# 2_classyTKL_MX_matrix.net
KiCad netlist of a schematic drawn in Altium Designer
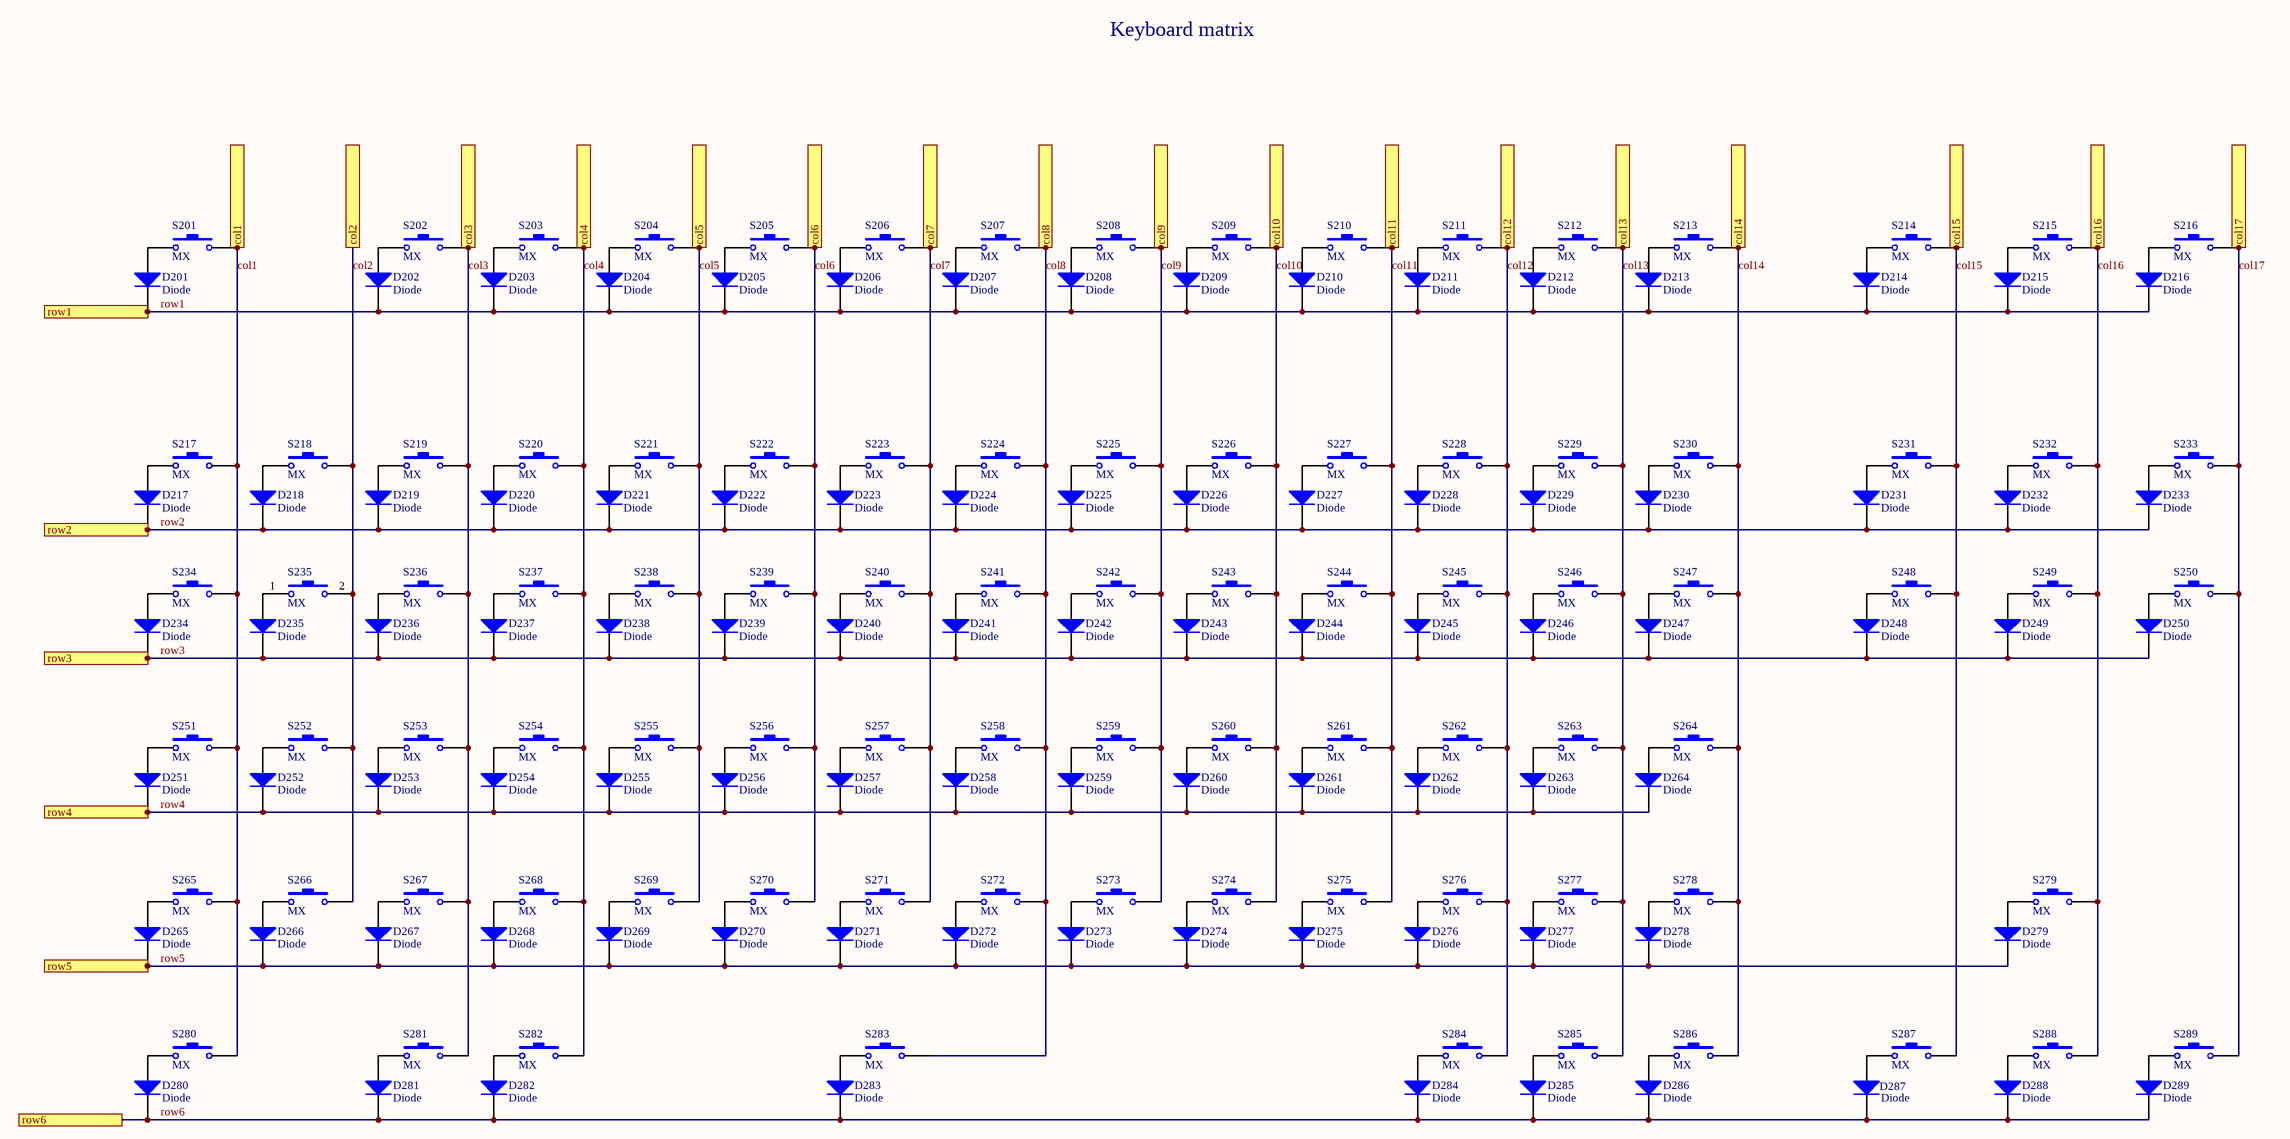
[diagram p0: 2_classyTKL_MX_matrix.SchDoc]

(export (version "E")
  (design (tool "Eeschema 10.0.6"))
  (components
    (comp (ref "D201")
      (value "Diode")
      (footprint "SOD-123")
      (description "Default Diode")
      (fields (field (name "LCSC PART #") "C81598") (field (name "MRF.PART") "1N4148W"))
      (libsource (lib "Miscellaneous Devices") (part "Diode"))
    )
    (comp (ref "D202")
      (value "Diode")
      (footprint "SOD-123")
      (description "Default Diode")
      (fields (field (name "LCSC PART #") "C81598") (field (name "MRF.PART") "1N4148W"))
      (libsource (lib "Miscellaneous Devices") (part "Diode"))
    )
    (comp (ref "D203")
      (value "Diode")
      (footprint "SOD-123")
      (description "Default Diode")
      (fields (field (name "LCSC PART #") "C81598") (field (name "MRF.PART") "1N4148W"))
      (libsource (lib "Miscellaneous Devices") (part "Diode"))
    )
    (comp (ref "D204")
      (value "Diode")
      (footprint "SOD-123")
      (description "Default Diode")
      (fields (field (name "LCSC PART #") "C81598") (field (name "MRF.PART") "1N4148W"))
      (libsource (lib "Miscellaneous Devices") (part "Diode"))
    )
    (comp (ref "D205")
      (value "Diode")
      (footprint "SOD-123")
      (description "Default Diode")
      (fields (field (name "LCSC PART #") "C81598") (field (name "MRF.PART") "1N4148W"))
      (libsource (lib "Miscellaneous Devices") (part "Diode"))
    )
    (comp (ref "D206")
      (value "Diode")
      (footprint "SOD-123")
      (description "Default Diode")
      (fields (field (name "LCSC PART #") "C81598") (field (name "MRF.PART") "1N4148W"))
      (libsource (lib "Miscellaneous Devices") (part "Diode"))
    )
    (comp (ref "D207")
      (value "Diode")
      (footprint "SOD-123")
      (description "Default Diode")
      (fields (field (name "LCSC PART #") "C81598") (field (name "MRF.PART") "1N4148W"))
      (libsource (lib "Miscellaneous Devices") (part "Diode"))
    )
    (comp (ref "D208")
      (value "Diode")
      (footprint "SOD-123")
      (description "Default Diode")
      (fields (field (name "LCSC PART #") "C81598") (field (name "MRF.PART") "1N4148W"))
      (libsource (lib "Miscellaneous Devices") (part "Diode"))
    )
    (comp (ref "D209")
      (value "Diode")
      (footprint "SOD-123")
      (description "Default Diode")
      (fields (field (name "LCSC PART #") "C81598") (field (name "MRF.PART") "1N4148W"))
      (libsource (lib "Miscellaneous Devices") (part "Diode"))
    )
    (comp (ref "D210")
      (value "Diode")
      (footprint "SOD-123")
      (description "Default Diode")
      (fields (field (name "LCSC PART #") "C81598") (field (name "MRF.PART") "1N4148W"))
      (libsource (lib "Miscellaneous Devices") (part "Diode"))
    )
    (comp (ref "D211")
      (value "Diode")
      (footprint "SOD-123")
      (description "Default Diode")
      (fields (field (name "LCSC PART #") "C81598") (field (name "MRF.PART") "1N4148W"))
      (libsource (lib "Miscellaneous Devices") (part "Diode"))
    )
    (comp (ref "D212")
      (value "Diode")
      (footprint "SOD-123")
      (description "Default Diode")
      (fields (field (name "LCSC PART #") "C81598") (field (name "MRF.PART") "1N4148W"))
      (libsource (lib "Miscellaneous Devices") (part "Diode"))
    )
    (comp (ref "D213")
      (value "Diode")
      (footprint "SOD-123")
      (description "Default Diode")
      (fields (field (name "LCSC PART #") "C81598") (field (name "MRF.PART") "1N4148W"))
      (libsource (lib "Miscellaneous Devices") (part "Diode"))
    )
    (comp (ref "D214")
      (value "Diode")
      (footprint "SOD-123")
      (description "Default Diode")
      (fields (field (name "LCSC PART #") "C81598") (field (name "MRF.PART") "1N4148W"))
      (libsource (lib "Miscellaneous Devices") (part "Diode"))
    )
    (comp (ref "D215")
      (value "Diode")
      (footprint "SOD-123")
      (description "Default Diode")
      (fields (field (name "LCSC PART #") "C81598") (field (name "MRF.PART") "1N4148W"))
      (libsource (lib "Miscellaneous Devices") (part "Diode"))
    )
    (comp (ref "D216")
      (value "Diode")
      (footprint "SOD-123")
      (description "Default Diode")
      (fields (field (name "LCSC PART #") "C81598") (field (name "MRF.PART") "1N4148W"))
      (libsource (lib "Miscellaneous Devices") (part "Diode"))
    )
    (comp (ref "D217")
      (value "Diode")
      (footprint "SOD-123")
      (description "Default Diode")
      (fields (field (name "LCSC PART #") "C81598") (field (name "MRF.PART") "1N4148W"))
      (libsource (lib "Miscellaneous Devices") (part "Diode"))
    )
    (comp (ref "D218")
      (value "Diode")
      (footprint "SOD-123")
      (description "Default Diode")
      (fields (field (name "LCSC PART #") "C81598") (field (name "MRF.PART") "1N4148W"))
      (libsource (lib "Miscellaneous Devices") (part "Diode"))
    )
    (comp (ref "D219")
      (value "Diode")
      (footprint "SOD-123")
      (description "Default Diode")
      (fields (field (name "LCSC PART #") "C81598") (field (name "MRF.PART") "1N4148W"))
      (libsource (lib "Miscellaneous Devices") (part "Diode"))
    )
    (comp (ref "D220")
      (value "Diode")
      (footprint "SOD-123")
      (description "Default Diode")
      (fields (field (name "LCSC PART #") "C81598") (field (name "MRF.PART") "1N4148W"))
      (libsource (lib "Miscellaneous Devices") (part "Diode"))
    )
    (comp (ref "D221")
      (value "Diode")
      (footprint "SOD-123")
      (description "Default Diode")
      (fields (field (name "LCSC PART #") "C81598") (field (name "MRF.PART") "1N4148W"))
      (libsource (lib "Miscellaneous Devices") (part "Diode"))
    )
    (comp (ref "D222")
      (value "Diode")
      (footprint "SOD-123")
      (description "Default Diode")
      (fields (field (name "LCSC PART #") "C81598") (field (name "MRF.PART") "1N4148W"))
      (libsource (lib "Miscellaneous Devices") (part "Diode"))
    )
    (comp (ref "D223")
      (value "Diode")
      (footprint "SOD-123")
      (description "Default Diode")
      (fields (field (name "LCSC PART #") "C81598") (field (name "MRF.PART") "1N4148W"))
      (libsource (lib "Miscellaneous Devices") (part "Diode"))
    )
    (comp (ref "D224")
      (value "Diode")
      (footprint "SOD-123")
      (description "Default Diode")
      (fields (field (name "LCSC PART #") "C81598") (field (name "MRF.PART") "1N4148W"))
      (libsource (lib "Miscellaneous Devices") (part "Diode"))
    )
    (comp (ref "D225")
      (value "Diode")
      (footprint "SOD-123")
      (description "Default Diode")
      (fields (field (name "LCSC PART #") "C81598") (field (name "MRF.PART") "1N4148W"))
      (libsource (lib "Miscellaneous Devices") (part "Diode"))
    )
    (comp (ref "D226")
      (value "Diode")
      (footprint "SOD-123")
      (description "Default Diode")
      (fields (field (name "LCSC PART #") "C81598") (field (name "MRF.PART") "1N4148W"))
      (libsource (lib "Miscellaneous Devices") (part "Diode"))
    )
    (comp (ref "D227")
      (value "Diode")
      (footprint "SOD-123")
      (description "Default Diode")
      (fields (field (name "LCSC PART #") "C81598") (field (name "MRF.PART") "1N4148W"))
      (libsource (lib "Miscellaneous Devices") (part "Diode"))
    )
    (comp (ref "D228")
      (value "Diode")
      (footprint "SOD-123")
      (description "Default Diode")
      (fields (field (name "LCSC PART #") "C81598") (field (name "MRF.PART") "1N4148W"))
      (libsource (lib "Miscellaneous Devices") (part "Diode"))
    )
    (comp (ref "D229")
      (value "Diode")
      (footprint "SOD-123")
      (description "Default Diode")
      (fields (field (name "LCSC PART #") "C81598") (field (name "MRF.PART") "1N4148W"))
      (libsource (lib "Miscellaneous Devices") (part "Diode"))
    )
    (comp (ref "D230")
      (value "Diode")
      (footprint "SOD-123")
      (description "Default Diode")
      (fields (field (name "LCSC PART #") "C81598") (field (name "MRF.PART") "1N4148W"))
      (libsource (lib "Miscellaneous Devices") (part "Diode"))
    )
    (comp (ref "D231")
      (value "Diode")
      (footprint "SOD-123")
      (description "Default Diode")
      (fields (field (name "LCSC PART #") "C81598") (field (name "MRF.PART") "1N4148W"))
      (libsource (lib "Miscellaneous Devices") (part "Diode"))
    )
    (comp (ref "D232")
      (value "Diode")
      (footprint "SOD-123")
      (description "Default Diode")
      (fields (field (name "LCSC PART #") "C81598") (field (name "MRF.PART") "1N4148W"))
      (libsource (lib "Miscellaneous Devices") (part "Diode"))
    )
    (comp (ref "D233")
      (value "Diode")
      (footprint "SOD-123")
      (description "Default Diode")
      (fields (field (name "LCSC PART #") "C81598") (field (name "MRF.PART") "1N4148W"))
      (libsource (lib "Miscellaneous Devices") (part "Diode"))
    )
    (comp (ref "D234")
      (value "Diode")
      (footprint "SOD-123")
      (description "Default Diode")
      (fields (field (name "LCSC PART #") "C81598") (field (name "MRF.PART") "1N4148W"))
      (libsource (lib "Miscellaneous Devices") (part "Diode"))
    )
    (comp (ref "D235")
      (value "Diode")
      (footprint "SOD-123")
      (description "Default Diode")
      (fields (field (name "LCSC PART #") "C81598") (field (name "MRF.PART") "1N4148W"))
      (libsource (lib "Miscellaneous Devices") (part "Diode"))
    )
    (comp (ref "D236")
      (value "Diode")
      (footprint "SOD-123")
      (description "Default Diode")
      (fields (field (name "LCSC PART #") "C81598") (field (name "MRF.PART") "1N4148W"))
      (libsource (lib "Miscellaneous Devices") (part "Diode"))
    )
    (comp (ref "D237")
      (value "Diode")
      (footprint "SOD-123")
      (description "Default Diode")
      (fields (field (name "LCSC PART #") "C81598") (field (name "MRF.PART") "1N4148W"))
      (libsource (lib "Miscellaneous Devices") (part "Diode"))
    )
    (comp (ref "D238")
      (value "Diode")
      (footprint "SOD-123")
      (description "Default Diode")
      (fields (field (name "LCSC PART #") "C81598") (field (name "MRF.PART") "1N4148W"))
      (libsource (lib "Miscellaneous Devices") (part "Diode"))
    )
    (comp (ref "D239")
      (value "Diode")
      (footprint "SOD-123")
      (description "Default Diode")
      (fields (field (name "LCSC PART #") "C81598") (field (name "MRF.PART") "1N4148W"))
      (libsource (lib "Miscellaneous Devices") (part "Diode"))
    )
    (comp (ref "D240")
      (value "Diode")
      (footprint "SOD-123")
      (description "Default Diode")
      (fields (field (name "LCSC PART #") "C81598") (field (name "MRF.PART") "1N4148W"))
      (libsource (lib "Miscellaneous Devices") (part "Diode"))
    )
    (comp (ref "D241")
      (value "Diode")
      (footprint "SOD-123")
      (description "Default Diode")
      (fields (field (name "LCSC PART #") "C81598") (field (name "MRF.PART") "1N4148W"))
      (libsource (lib "Miscellaneous Devices") (part "Diode"))
    )
    (comp (ref "D242")
      (value "Diode")
      (footprint "SOD-123")
      (description "Default Diode")
      (fields (field (name "LCSC PART #") "C81598") (field (name "MRF.PART") "1N4148W"))
      (libsource (lib "Miscellaneous Devices") (part "Diode"))
    )
    (comp (ref "D243")
      (value "Diode")
      (footprint "SOD-123")
      (description "Default Diode")
      (fields (field (name "LCSC PART #") "C81598") (field (name "MRF.PART") "1N4148W"))
      (libsource (lib "Miscellaneous Devices") (part "Diode"))
    )
    (comp (ref "D244")
      (value "Diode")
      (footprint "SOD-123")
      (description "Default Diode")
      (fields (field (name "LCSC PART #") "C81598") (field (name "MRF.PART") "1N4148W"))
      (libsource (lib "Miscellaneous Devices") (part "Diode"))
    )
    (comp (ref "D245")
      (value "Diode")
      (footprint "SOD-123")
      (description "Default Diode")
      (fields (field (name "LCSC PART #") "C81598") (field (name "MRF.PART") "1N4148W"))
      (libsource (lib "Miscellaneous Devices") (part "Diode"))
    )
    (comp (ref "D246")
      (value "Diode")
      (footprint "SOD-123")
      (description "Default Diode")
      (fields (field (name "LCSC PART #") "C81598") (field (name "MRF.PART") "1N4148W"))
      (libsource (lib "Miscellaneous Devices") (part "Diode"))
    )
    (comp (ref "D247")
      (value "Diode")
      (footprint "SOD-123")
      (description "Default Diode")
      (fields (field (name "LCSC PART #") "C81598") (field (name "MRF.PART") "1N4148W"))
      (libsource (lib "Miscellaneous Devices") (part "Diode"))
    )
    (comp (ref "D248")
      (value "Diode")
      (footprint "SOD-123")
      (description "Default Diode")
      (fields (field (name "LCSC PART #") "C81598") (field (name "MRF.PART") "1N4148W"))
      (libsource (lib "Miscellaneous Devices") (part "Diode"))
    )
    (comp (ref "D249")
      (value "Diode")
      (footprint "SOD-123")
      (description "Default Diode")
      (fields (field (name "LCSC PART #") "C81598") (field (name "MRF.PART") "1N4148W"))
      (libsource (lib "Miscellaneous Devices") (part "Diode"))
    )
    (comp (ref "D250")
      (value "Diode")
      (footprint "SOD-123")
      (description "Default Diode")
      (fields (field (name "LCSC PART #") "C81598") (field (name "MRF.PART") "1N4148W"))
      (libsource (lib "Miscellaneous Devices") (part "Diode"))
    )
    (comp (ref "D251")
      (value "Diode")
      (footprint "SOD-123")
      (description "Default Diode")
      (fields (field (name "LCSC PART #") "C81598") (field (name "MRF.PART") "1N4148W"))
      (libsource (lib "Miscellaneous Devices") (part "Diode"))
    )
    (comp (ref "D252")
      (value "Diode")
      (footprint "SOD-123")
      (description "Default Diode")
      (fields (field (name "LCSC PART #") "C81598") (field (name "MRF.PART") "1N4148W"))
      (libsource (lib "Miscellaneous Devices") (part "Diode"))
    )
    (comp (ref "D253")
      (value "Diode")
      (footprint "SOD-123")
      (description "Default Diode")
      (fields (field (name "LCSC PART #") "C81598") (field (name "MRF.PART") "1N4148W"))
      (libsource (lib "Miscellaneous Devices") (part "Diode"))
    )
    (comp (ref "D254")
      (value "Diode")
      (footprint "SOD-123")
      (description "Default Diode")
      (fields (field (name "LCSC PART #") "C81598") (field (name "MRF.PART") "1N4148W"))
      (libsource (lib "Miscellaneous Devices") (part "Diode"))
    )
    (comp (ref "D255")
      (value "Diode")
      (footprint "SOD-123")
      (description "Default Diode")
      (fields (field (name "LCSC PART #") "C81598") (field (name "MRF.PART") "1N4148W"))
      (libsource (lib "Miscellaneous Devices") (part "Diode"))
    )
    (comp (ref "D256")
      (value "Diode")
      (footprint "SOD-123")
      (description "Default Diode")
      (fields (field (name "LCSC PART #") "C81598") (field (name "MRF.PART") "1N4148W"))
      (libsource (lib "Miscellaneous Devices") (part "Diode"))
    )
    (comp (ref "D257")
      (value "Diode")
      (footprint "SOD-123")
      (description "Default Diode")
      (fields (field (name "LCSC PART #") "C81598") (field (name "MRF.PART") "1N4148W"))
      (libsource (lib "Miscellaneous Devices") (part "Diode"))
    )
    (comp (ref "D258")
      (value "Diode")
      (footprint "SOD-123")
      (description "Default Diode")
      (fields (field (name "LCSC PART #") "C81598") (field (name "MRF.PART") "1N4148W"))
      (libsource (lib "Miscellaneous Devices") (part "Diode"))
    )
    (comp (ref "D259")
      (value "Diode")
      (footprint "SOD-123")
      (description "Default Diode")
      (fields (field (name "LCSC PART #") "C81598") (field (name "MRF.PART") "1N4148W"))
      (libsource (lib "Miscellaneous Devices") (part "Diode"))
    )
    (comp (ref "D260")
      (value "Diode")
      (footprint "SOD-123")
      (description "Default Diode")
      (fields (field (name "LCSC PART #") "C81598") (field (name "MRF.PART") "1N4148W"))
      (libsource (lib "Miscellaneous Devices") (part "Diode"))
    )
    (comp (ref "D261")
      (value "Diode")
      (footprint "SOD-123")
      (description "Default Diode")
      (fields (field (name "LCSC PART #") "C81598") (field (name "MRF.PART") "1N4148W"))
      (libsource (lib "Miscellaneous Devices") (part "Diode"))
    )
    (comp (ref "D262")
      (value "Diode")
      (footprint "SOD-123")
      (description "Default Diode")
      (fields (field (name "LCSC PART #") "C81598") (field (name "MRF.PART") "1N4148W"))
      (libsource (lib "Miscellaneous Devices") (part "Diode"))
    )
    (comp (ref "D263")
      (value "Diode")
      (footprint "SOD-123")
      (description "Default Diode")
      (fields (field (name "LCSC PART #") "C81598") (field (name "MRF.PART") "1N4148W"))
      (libsource (lib "Miscellaneous Devices") (part "Diode"))
    )
    (comp (ref "D264")
      (value "Diode")
      (footprint "SOD-123")
      (description "Default Diode")
      (fields (field (name "LCSC PART #") "C81598") (field (name "MRF.PART") "1N4148W"))
      (libsource (lib "Miscellaneous Devices") (part "Diode"))
    )
    (comp (ref "D265")
      (value "Diode")
      (footprint "SOD-123")
      (description "Default Diode")
      (fields (field (name "LCSC PART #") "C81598") (field (name "MRF.PART") "1N4148W"))
      (libsource (lib "Miscellaneous Devices") (part "Diode"))
    )
    (comp (ref "D266")
      (value "Diode")
      (footprint "SOD-123")
      (description "Default Diode")
      (fields (field (name "LCSC PART #") "C81598") (field (name "MRF.PART") "1N4148W"))
      (libsource (lib "Miscellaneous Devices") (part "Diode"))
    )
    (comp (ref "D267")
      (value "Diode")
      (footprint "SOD-123")
      (description "Default Diode")
      (fields (field (name "LCSC PART #") "C81598") (field (name "MRF.PART") "1N4148W"))
      (libsource (lib "Miscellaneous Devices") (part "Diode"))
    )
    (comp (ref "D268")
      (value "Diode")
      (footprint "SOD-123")
      (description "Default Diode")
      (fields (field (name "LCSC PART #") "C81598") (field (name "MRF.PART") "1N4148W"))
      (libsource (lib "Miscellaneous Devices") (part "Diode"))
    )
    (comp (ref "D269")
      (value "Diode")
      (footprint "SOD-123")
      (description "Default Diode")
      (fields (field (name "LCSC PART #") "C81598") (field (name "MRF.PART") "1N4148W"))
      (libsource (lib "Miscellaneous Devices") (part "Diode"))
    )
    (comp (ref "D270")
      (value "Diode")
      (footprint "SOD-123")
      (description "Default Diode")
      (fields (field (name "LCSC PART #") "C81598") (field (name "MRF.PART") "1N4148W"))
      (libsource (lib "Miscellaneous Devices") (part "Diode"))
    )
    (comp (ref "D271")
      (value "Diode")
      (footprint "SOD-123")
      (description "Default Diode")
      (fields (field (name "LCSC PART #") "C81598") (field (name "MRF.PART") "1N4148W"))
      (libsource (lib "Miscellaneous Devices") (part "Diode"))
    )
    (comp (ref "D272")
      (value "Diode")
      (footprint "SOD-123")
      (description "Default Diode")
      (fields (field (name "LCSC PART #") "C81598") (field (name "MRF.PART") "1N4148W"))
      (libsource (lib "Miscellaneous Devices") (part "Diode"))
    )
    (comp (ref "D273")
      (value "Diode")
      (footprint "SOD-123")
      (description "Default Diode")
      (fields (field (name "LCSC PART #") "C81598") (field (name "MRF.PART") "1N4148W"))
      (libsource (lib "Miscellaneous Devices") (part "Diode"))
    )
    (comp (ref "D274")
      (value "Diode")
      (footprint "SOD-123")
      (description "Default Diode")
      (fields (field (name "LCSC PART #") "C81598") (field (name "MRF.PART") "1N4148W"))
      (libsource (lib "Miscellaneous Devices") (part "Diode"))
    )
    (comp (ref "D275")
      (value "Diode")
      (footprint "SOD-123")
      (description "Default Diode")
      (fields (field (name "LCSC PART #") "C81598") (field (name "MRF.PART") "1N4148W"))
      (libsource (lib "Miscellaneous Devices") (part "Diode"))
    )
    (comp (ref "D276")
      (value "Diode")
      (footprint "SOD-123")
      (description "Default Diode")
      (fields (field (name "LCSC PART #") "C81598") (field (name "MRF.PART") "1N4148W"))
      (libsource (lib "Miscellaneous Devices") (part "Diode"))
    )
    (comp (ref "D277")
      (value "Diode")
      (footprint "SOD-123")
      (description "Default Diode")
      (fields (field (name "LCSC PART #") "C81598") (field (name "MRF.PART") "1N4148W"))
      (libsource (lib "Miscellaneous Devices") (part "Diode"))
    )
    (comp (ref "D278")
      (value "Diode")
      (footprint "SOD-123")
      (description "Default Diode")
      (fields (field (name "LCSC PART #") "C81598") (field (name "MRF.PART") "1N4148W"))
      (libsource (lib "Miscellaneous Devices") (part "Diode"))
    )
    (comp (ref "D279")
      (value "Diode")
      (footprint "SOD-123")
      (description "Default Diode")
      (fields (field (name "LCSC PART #") "C81598") (field (name "MRF.PART") "1N4148W"))
      (libsource (lib "Miscellaneous Devices") (part "Diode"))
    )
    (comp (ref "D280")
      (value "Diode")
      (footprint "SOD-123")
      (description "Default Diode")
      (fields (field (name "LCSC PART #") "C81598") (field (name "MRF.PART") "1N4148W"))
      (libsource (lib "Miscellaneous Devices") (part "Diode"))
    )
    (comp (ref "D281")
      (value "Diode")
      (footprint "SOD-123")
      (description "Default Diode")
      (fields (field (name "LCSC PART #") "C81598") (field (name "MRF.PART") "1N4148W"))
      (libsource (lib "Miscellaneous Devices") (part "Diode"))
    )
    (comp (ref "D282")
      (value "Diode")
      (footprint "SOD-123")
      (description "Default Diode")
      (fields (field (name "LCSC PART #") "C81598") (field (name "MRF.PART") "1N4148W"))
      (libsource (lib "Miscellaneous Devices") (part "Diode"))
    )
    (comp (ref "D283")
      (value "Diode")
      (footprint "SOD-123")
      (description "Default Diode")
      (fields (field (name "LCSC PART #") "C81598") (field (name "MRF.PART") "1N4148W"))
      (libsource (lib "Miscellaneous Devices") (part "Diode"))
    )
    (comp (ref "D284")
      (value "Diode")
      (footprint "SOD-123")
      (description "Default Diode")
      (fields (field (name "LCSC PART #") "C81598") (field (name "MRF.PART") "1N4148W"))
      (libsource (lib "Miscellaneous Devices") (part "Diode"))
    )
    (comp (ref "D285")
      (value "Diode")
      (footprint "SOD-123")
      (description "Default Diode")
      (fields (field (name "LCSC PART #") "C81598") (field (name "MRF.PART") "1N4148W"))
      (libsource (lib "Miscellaneous Devices") (part "Diode"))
    )
    (comp (ref "D286")
      (value "Diode")
      (footprint "SOD-123")
      (description "Default Diode")
      (fields (field (name "LCSC PART #") "C81598") (field (name "MRF.PART") "1N4148W"))
      (libsource (lib "Miscellaneous Devices") (part "Diode"))
    )
    (comp (ref "D287")
      (value "Diode")
      (footprint "SOD-123")
      (description "Default Diode")
      (fields (field (name "LCSC PART #") "C81598") (field (name "MRF.PART") "1N4148W"))
      (libsource (lib "Miscellaneous Devices") (part "Diode"))
    )
    (comp (ref "D288")
      (value "Diode")
      (footprint "SOD-123")
      (description "Default Diode")
      (fields (field (name "LCSC PART #") "C81598") (field (name "MRF.PART") "1N4148W"))
      (libsource (lib "Miscellaneous Devices") (part "Diode"))
    )
    (comp (ref "D289")
      (value "Diode")
      (footprint "SOD-123")
      (description "Default Diode")
      (fields (field (name "LCSC PART #") "C81598") (field (name "MRF.PART") "1N4148W"))
      (libsource (lib "Miscellaneous Devices") (part "Diode"))
    )
    (comp (ref "S201")
      (value "MX")
      (footprint "MX-switch - switched pol")
      (description "Switch")
      (libsource (lib "Miscellaneous Devices") (part "SW-PB"))
    )
    (comp (ref "S202")
      (value "MX")
      (footprint "MX-switch")
      (description "Switch")
      (libsource (lib "Miscellaneous Devices") (part "SW-PB"))
    )
    (comp (ref "S203")
      (value "MX")
      (footprint "MX-switch")
      (description "Switch")
      (libsource (lib "Miscellaneous Devices") (part "SW-PB"))
    )
    (comp (ref "S204")
      (value "MX")
      (footprint "MX-switch")
      (description "Switch")
      (libsource (lib "Miscellaneous Devices") (part "SW-PB"))
    )
    (comp (ref "S205")
      (value "MX")
      (footprint "MX-switch - switched pol")
      (description "Switch")
      (libsource (lib "Miscellaneous Devices") (part "SW-PB"))
    )
    (comp (ref "S206")
      (value "MX")
      (footprint "MX-switch")
      (description "Switch")
      (libsource (lib "Miscellaneous Devices") (part "SW-PB"))
    )
    (comp (ref "S207")
      (value "MX")
      (footprint "MX-switch")
      (description "Switch")
      (libsource (lib "Miscellaneous Devices") (part "SW-PB"))
    )
    (comp (ref "S208")
      (value "MX")
      (footprint "MX-switch")
      (description "Switch")
      (libsource (lib "Miscellaneous Devices") (part "SW-PB"))
    )
    (comp (ref "S209")
      (value "MX")
      (footprint "MX-switch")
      (description "Switch")
      (libsource (lib "Miscellaneous Devices") (part "SW-PB"))
    )
    (comp (ref "S210")
      (value "MX")
      (footprint "MX-switch")
      (description "Switch")
      (libsource (lib "Miscellaneous Devices") (part "SW-PB"))
    )
    (comp (ref "S211")
      (value "MX")
      (footprint "MX-switch")
      (description "Switch")
      (libsource (lib "Miscellaneous Devices") (part "SW-PB"))
    )
    (comp (ref "S212")
      (value "MX")
      (footprint "MX-switch")
      (description "Switch")
      (libsource (lib "Miscellaneous Devices") (part "SW-PB"))
    )
    (comp (ref "S213")
      (value "MX")
      (footprint "MX-switch")
      (description "Switch")
      (libsource (lib "Miscellaneous Devices") (part "SW-PB"))
    )
    (comp (ref "S214")
      (value "MX")
      (footprint "MX-switch")
      (description "Switch")
      (libsource (lib "Miscellaneous Devices") (part "SW-PB"))
    )
    (comp (ref "S215")
      (value "MX")
      (footprint "MX-switch")
      (description "Switch")
      (libsource (lib "Miscellaneous Devices") (part "SW-PB"))
    )
    (comp (ref "S216")
      (value "MX")
      (footprint "MX-switch")
      (description "Switch")
      (libsource (lib "Miscellaneous Devices") (part "SW-PB"))
    )
    (comp (ref "S217")
      (value "MX")
      (footprint "MX-switch - switched pol")
      (description "Switch")
      (libsource (lib "Miscellaneous Devices") (part "SW-PB"))
    )
    (comp (ref "S218")
      (value "MX")
      (footprint "MX-switch - switched pol")
      (description "Switch")
      (libsource (lib "Miscellaneous Devices") (part "SW-PB"))
    )
    (comp (ref "S219")
      (value "MX")
      (footprint "MX-switch - switched pol")
      (description "Switch")
      (libsource (lib "Miscellaneous Devices") (part "SW-PB"))
    )
    (comp (ref "S220")
      (value "MX")
      (footprint "MX-switch - switched pol")
      (description "Switch")
      (libsource (lib "Miscellaneous Devices") (part "SW-PB"))
    )
    (comp (ref "S221")
      (value "MX")
      (footprint "MX-switch - switched pol")
      (description "Switch")
      (libsource (lib "Miscellaneous Devices") (part "SW-PB"))
    )
    (comp (ref "S222")
      (value "MX")
      (footprint "MX-switch - switched pol")
      (description "Switch")
      (libsource (lib "Miscellaneous Devices") (part "SW-PB"))
    )
    (comp (ref "S223")
      (value "MX")
      (footprint "MX-switch - switched pol")
      (description "Switch")
      (libsource (lib "Miscellaneous Devices") (part "SW-PB"))
    )
    (comp (ref "S224")
      (value "MX")
      (footprint "MX-switch - switched pol")
      (description "Switch")
      (libsource (lib "Miscellaneous Devices") (part "SW-PB"))
    )
    (comp (ref "S225")
      (value "MX")
      (footprint "MX-switch - switched pol")
      (description "Switch")
      (libsource (lib "Miscellaneous Devices") (part "SW-PB"))
    )
    (comp (ref "S226")
      (value "MX")
      (footprint "MX-switch - switched pol")
      (description "Switch")
      (libsource (lib "Miscellaneous Devices") (part "SW-PB"))
    )
    (comp (ref "S227")
      (value "MX")
      (footprint "MX-switch - switched pol")
      (description "Switch")
      (libsource (lib "Miscellaneous Devices") (part "SW-PB"))
    )
    (comp (ref "S228")
      (value "MX")
      (footprint "MX-switch - switched pol")
      (description "Switch")
      (libsource (lib "Miscellaneous Devices") (part "SW-PB"))
    )
    (comp (ref "S229")
      (value "MX")
      (footprint "MX-switch - switched pol")
      (description "Switch")
      (libsource (lib "Miscellaneous Devices") (part "SW-PB"))
    )
    (comp (ref "S230")
      (value "MX")
      (footprint "MX-switch")
      (description "Switch")
      (libsource (lib "Miscellaneous Devices") (part "SW-PB"))
    )
    (comp (ref "S231")
      (value "MX")
      (footprint "MX-switch")
      (description "Switch")
      (libsource (lib "Miscellaneous Devices") (part "SW-PB"))
    )
    (comp (ref "S232")
      (value "MX")
      (footprint "MX-switch")
      (description "Switch")
      (libsource (lib "Miscellaneous Devices") (part "SW-PB"))
    )
    (comp (ref "S233")
      (value "MX")
      (footprint "MX-switch")
      (description "Switch")
      (libsource (lib "Miscellaneous Devices") (part "SW-PB"))
    )
    (comp (ref "S234")
      (value "MX")
      (footprint "MX-switch - 1.5U - switched pol")
      (description "TAB")
      (libsource (lib "Miscellaneous Devices") (part "SW-PB"))
    )
    (comp (ref "S235")
      (value "MX")
      (footprint "MX-switch - switched pol")
      (description "Switch")
      (libsource (lib "") (part "SW-PB_1"))
    )
    (comp (ref "S236")
      (value "MX")
      (footprint "MX-switch - switched pol")
      (description "Switch")
      (libsource (lib "Miscellaneous Devices") (part "SW-PB"))
    )
    (comp (ref "S237")
      (value "MX")
      (footprint "MX-switch - switched pol")
      (description "Switch")
      (libsource (lib "Miscellaneous Devices") (part "SW-PB"))
    )
    (comp (ref "S238")
      (value "MX")
      (footprint "MX-switch - switched pol")
      (description "Switch")
      (libsource (lib "Miscellaneous Devices") (part "SW-PB"))
    )
    (comp (ref "S239")
      (value "MX")
      (footprint "MX-switch - switched pol")
      (description "Switch")
      (libsource (lib "Miscellaneous Devices") (part "SW-PB"))
    )
    (comp (ref "S240")
      (value "MX")
      (footprint "MX-switch - switched pol")
      (description "Switch")
      (libsource (lib "Miscellaneous Devices") (part "SW-PB"))
    )
    (comp (ref "S241")
      (value "MX")
      (footprint "MX-switch - switched pol")
      (description "Switch")
      (libsource (lib "Miscellaneous Devices") (part "SW-PB"))
    )
    (comp (ref "S242")
      (value "MX")
      (footprint "MX-switch - switched pol")
      (description "Switch")
      (libsource (lib "Miscellaneous Devices") (part "SW-PB"))
    )
    (comp (ref "S243")
      (value "MX")
      (footprint "MX-switch - switched pol")
      (description "Switch")
      (libsource (lib "Miscellaneous Devices") (part "SW-PB"))
    )
    (comp (ref "S244")
      (value "MX")
      (footprint "MX-switch - switched pol")
      (description "Switch")
      (libsource (lib "Miscellaneous Devices") (part "SW-PB"))
    )
    (comp (ref "S245")
      (value "MX")
      (footprint "MX-switch - switched pol")
      (description "Switch")
      (libsource (lib "Miscellaneous Devices") (part "SW-PB"))
    )
    (comp (ref "S246")
      (value "MX")
      (footprint "MX-switch - switched pol")
      (description "Switch")
      (libsource (lib "Miscellaneous Devices") (part "SW-PB"))
    )
    (comp (ref "S247")
      (value "MX")
      (footprint "MX-switch - PIPE_ISO_ENTER")
      (description "Switch")
      (libsource (lib "Miscellaneous Devices") (part "SW-PB"))
    )
    (comp (ref "S248")
      (value "MX")
      (footprint "MX-switch")
      (description "Switch")
      (libsource (lib "Miscellaneous Devices") (part "SW-PB"))
    )
    (comp (ref "S249")
      (value "MX")
      (footprint "MX-switch")
      (description "Switch")
      (libsource (lib "Miscellaneous Devices") (part "SW-PB"))
    )
    (comp (ref "S250")
      (value "MX")
      (footprint "MX-switch")
      (description "Switch")
      (libsource (lib "Miscellaneous Devices") (part "SW-PB"))
    )
    (comp (ref "S251")
      (value "MX")
      (footprint "MX-switch - CAPS")
      (description "Switch")
      (libsource (lib "Miscellaneous Devices") (part "SW-PB"))
    )
    (comp (ref "S252")
      (value "MX")
      (footprint "MX-switch - switched pol")
      (description "Switch")
      (libsource (lib "Miscellaneous Devices") (part "SW-PB"))
    )
    (comp (ref "S253")
      (value "MX")
      (footprint "MX-switch - switched pol")
      (description "Switch")
      (libsource (lib "Miscellaneous Devices") (part "SW-PB"))
    )
    (comp (ref "S254")
      (value "MX")
      (footprint "MX-switch - switched pol")
      (description "Switch")
      (libsource (lib "Miscellaneous Devices") (part "SW-PB"))
    )
    (comp (ref "S255")
      (value "MX")
      (footprint "MX-switch - switched pol")
      (description "Switch")
      (libsource (lib "Miscellaneous Devices") (part "SW-PB"))
    )
    (comp (ref "S256")
      (value "MX")
      (footprint "MX-switch - switched pol")
      (description "Switch")
      (libsource (lib "Miscellaneous Devices") (part "SW-PB"))
    )
    (comp (ref "S257")
      (value "MX")
      (footprint "MX-switch - switched pol")
      (description "Switch")
      (libsource (lib "Miscellaneous Devices") (part "SW-PB"))
    )
    (comp (ref "S258")
      (value "MX")
      (footprint "MX-switch - switched pol")
      (description "Switch")
      (libsource (lib "Miscellaneous Devices") (part "SW-PB"))
    )
    (comp (ref "S259")
      (value "MX")
      (footprint "MX-switch - switched pol")
      (description "Switch")
      (libsource (lib "Miscellaneous Devices") (part "SW-PB"))
    )
    (comp (ref "S260")
      (value "MX")
      (footprint "MX-switch - switched pol")
      (description "Switch")
      (libsource (lib "Miscellaneous Devices") (part "SW-PB"))
    )
    (comp (ref "S261")
      (value "MX")
      (footprint "MX-switch - switched pol")
      (description "Switch")
      (libsource (lib "Miscellaneous Devices") (part "SW-PB"))
    )
    (comp (ref "S262")
      (value "MX")
      (footprint "MX-switch - switched pol")
      (description "Switch")
      (libsource (lib "Miscellaneous Devices") (part "SW-PB"))
    )
    (comp (ref "S263")
      (value "MX")
      (footprint "MX-switch - Enter_ANSI_ISO_KEY")
      (description "Switch")
      (libsource (lib "Miscellaneous Devices") (part "SW-PB"))
    )
    (comp (ref "S264")
      (value "MX")
      (footprint "MX-switch - backspace")
      (description "Switch")
      (libsource (lib "Miscellaneous Devices") (part "SW-PB"))
    )
    (comp (ref "S265")
      (value "MX")
      (footprint "MX-switch - Left shift")
      (description "Switch")
      (libsource (lib "Miscellaneous Devices") (part "SW-PB"))
    )
    (comp (ref "S266")
      (value "MX")
      (footprint "MX-switch - switched pol")
      (description "Switch")
      (libsource (lib "Miscellaneous Devices") (part "SW-PB"))
    )
    (comp (ref "S267")
      (value "MX")
      (footprint "MX-switch - switched pol")
      (description "Switch")
      (libsource (lib "Miscellaneous Devices") (part "SW-PB"))
    )
    (comp (ref "S268")
      (value "MX")
      (footprint "MX-switch - switched pol")
      (description "Switch")
      (libsource (lib "Miscellaneous Devices") (part "SW-PB"))
    )
    (comp (ref "S269")
      (value "MX")
      (footprint "MX-switch - switched pol")
      (description "Switch")
      (libsource (lib "Miscellaneous Devices") (part "SW-PB"))
    )
    (comp (ref "S270")
      (value "MX")
      (footprint "MX-switch - switched pol")
      (description "Switch")
      (libsource (lib "Miscellaneous Devices") (part "SW-PB"))
    )
    (comp (ref "S271")
      (value "MX")
      (footprint "MX-switch - switched pol")
      (description "Switch")
      (libsource (lib "Miscellaneous Devices") (part "SW-PB"))
    )
    (comp (ref "S272")
      (value "MX")
      (footprint "MX-switch - switched pol")
      (description "Switch")
      (libsource (lib "Miscellaneous Devices") (part "SW-PB"))
    )
    (comp (ref "S273")
      (value "MX")
      (footprint "MX-switch - switched pol")
      (description "Switch")
      (libsource (lib "Miscellaneous Devices") (part "SW-PB"))
    )
    (comp (ref "S274")
      (value "MX")
      (footprint "MX-switch - switched pol")
      (description "Switch")
      (libsource (lib "Miscellaneous Devices") (part "SW-PB"))
    )
    (comp (ref "S275")
      (value "MX")
      (footprint "MX-switch - switched pol")
      (description "Switch")
      (libsource (lib "Miscellaneous Devices") (part "SW-PB"))
    )
    (comp (ref "S276")
      (value "MX")
      (footprint "MX-switch - switched pol")
      (description "Switch")
      (libsource (lib "Miscellaneous Devices") (part "SW-PB"))
    )
    (comp (ref "S277")
      (value "MX")
      (footprint "MX-switch - right shift")
      (description "Switch")
      (libsource (lib "Miscellaneous Devices") (part "SW-PB"))
    )
    (comp (ref "S278")
      (value "MX")
      (footprint "MX-switch")
      (description "Switch")
      (libsource (lib "Miscellaneous Devices") (part "SW-PB"))
    )
    (comp (ref "S279")
      (value "MX")
      (footprint "MX-switch")
      (description "Switch")
      (libsource (lib "Miscellaneous Devices") (part "SW-PB"))
    )
    (comp (ref "S280")
      (value "MX")
      (footprint "MX-switch - 1.5U - switched pol")
      (description "Switch")
      (libsource (lib "Miscellaneous Devices") (part "SW-PB"))
    )
    (comp (ref "S281")
      (value "MX")
      (footprint "MX-switch")
      (description "Switch")
      (libsource (lib "Miscellaneous Devices") (part "SW-PB"))
    )
    (comp (ref "S282")
      (value "MX")
      (footprint "MX-switch - 1.5U")
      (description "Switch")
      (libsource (lib "Miscellaneous Devices") (part "SW-PB"))
    )
    (comp (ref "S283")
      (value "MX")
      (footprint "MX-switch - 7u space")
      (description "Switch")
      (libsource (lib "Miscellaneous Devices") (part "SW-PB"))
    )
    (comp (ref "S284")
      (value "MX")
      (footprint "MX-switch - 1.5U")
      (description "Switch")
      (libsource (lib "Miscellaneous Devices") (part "SW-PB"))
    )
    (comp (ref "S285")
      (value "MX")
      (footprint "MX-switch")
      (description "Switch")
      (libsource (lib "Miscellaneous Devices") (part "SW-PB"))
    )
    (comp (ref "S286")
      (value "MX")
      (footprint "MX-switch - 1.5U")
      (description "Switch")
      (libsource (lib "Miscellaneous Devices") (part "SW-PB"))
    )
    (comp (ref "S287")
      (value "MX")
      (footprint "MX-switch")
      (description "Switch")
      (libsource (lib "Miscellaneous Devices") (part "SW-PB"))
    )
    (comp (ref "S288")
      (value "MX")
      (footprint "MX-switch")
      (description "Switch")
      (libsource (lib "Miscellaneous Devices") (part "SW-PB"))
    )
    (comp (ref "S289")
      (value "MX")
      (footprint "MX-switch")
      (description "Switch")
      (libsource (lib "Miscellaneous Devices") (part "SW-PB"))
    )
  )
  (nets
    (net (code "1") (name "/col1") (class "Default")
      (node (ref "S201") (pin "2") (pinfunction "2_2") (pintype "passive"))
      (node (ref "S217") (pin "2") (pinfunction "2_2") (pintype "passive"))
      (node (ref "S234") (pin "2") (pinfunction "2_2") (pintype "passive"))
      (node (ref "S251") (pin "2") (pinfunction "2_2") (pintype "passive"))
      (node (ref "S265") (pin "2") (pinfunction "2_2") (pintype "passive"))
      (node (ref "S280") (pin "2") (pinfunction "2_2") (pintype "passive"))
    )
    (net (code "2") (name "/col2") (class "Default")
      (node (ref "S218") (pin "2") (pinfunction "2_2") (pintype "passive"))
      (node (ref "S235") (pin "2") (pinfunction "2_2") (pintype "passive"))
      (node (ref "S252") (pin "2") (pinfunction "2_2") (pintype "passive"))
      (node (ref "S266") (pin "2") (pinfunction "2_2") (pintype "passive"))
    )
    (net (code "3") (name "/col3") (class "Default")
      (node (ref "S202") (pin "2") (pinfunction "2_2") (pintype "passive"))
      (node (ref "S219") (pin "2") (pinfunction "2_2") (pintype "passive"))
      (node (ref "S236") (pin "2") (pinfunction "2_2") (pintype "passive"))
      (node (ref "S253") (pin "2") (pinfunction "2_2") (pintype "passive"))
      (node (ref "S267") (pin "2") (pinfunction "2_2") (pintype "passive"))
      (node (ref "S281") (pin "2") (pinfunction "2_2") (pintype "passive"))
    )
    (net (code "4") (name "/col4") (class "Default")
      (node (ref "S203") (pin "2") (pinfunction "2_2") (pintype "passive"))
      (node (ref "S220") (pin "2") (pinfunction "2_2") (pintype "passive"))
      (node (ref "S237") (pin "2") (pinfunction "2_2") (pintype "passive"))
      (node (ref "S254") (pin "2") (pinfunction "2_2") (pintype "passive"))
      (node (ref "S268") (pin "2") (pinfunction "2_2") (pintype "passive"))
      (node (ref "S282") (pin "2") (pinfunction "2_2") (pintype "passive"))
    )
    (net (code "5") (name "/col5") (class "Default")
      (node (ref "S204") (pin "2") (pinfunction "2_2") (pintype "passive"))
      (node (ref "S221") (pin "2") (pinfunction "2_2") (pintype "passive"))
      (node (ref "S238") (pin "2") (pinfunction "2_2") (pintype "passive"))
      (node (ref "S255") (pin "2") (pinfunction "2_2") (pintype "passive"))
      (node (ref "S269") (pin "2") (pinfunction "2_2") (pintype "passive"))
    )
    (net (code "6") (name "/col6") (class "Default")
      (node (ref "S205") (pin "2") (pinfunction "2_2") (pintype "passive"))
      (node (ref "S222") (pin "2") (pinfunction "2_2") (pintype "passive"))
      (node (ref "S239") (pin "2") (pinfunction "2_2") (pintype "passive"))
      (node (ref "S256") (pin "2") (pinfunction "2_2") (pintype "passive"))
      (node (ref "S270") (pin "2") (pinfunction "2_2") (pintype "passive"))
    )
    (net (code "7") (name "/col7") (class "Default")
      (node (ref "S206") (pin "2") (pinfunction "2_2") (pintype "passive"))
      (node (ref "S223") (pin "2") (pinfunction "2_2") (pintype "passive"))
      (node (ref "S240") (pin "2") (pinfunction "2_2") (pintype "passive"))
      (node (ref "S257") (pin "2") (pinfunction "2_2") (pintype "passive"))
      (node (ref "S271") (pin "2") (pinfunction "2_2") (pintype "passive"))
    )
    (net (code "8") (name "/col8") (class "Default")
      (node (ref "S207") (pin "2") (pinfunction "2_2") (pintype "passive"))
      (node (ref "S224") (pin "2") (pinfunction "2_2") (pintype "passive"))
      (node (ref "S241") (pin "2") (pinfunction "2_2") (pintype "passive"))
      (node (ref "S258") (pin "2") (pinfunction "2_2") (pintype "passive"))
      (node (ref "S272") (pin "2") (pinfunction "2_2") (pintype "passive"))
      (node (ref "S283") (pin "2") (pinfunction "2_2") (pintype "passive"))
    )
    (net (code "9") (name "/col9") (class "Default")
      (node (ref "S208") (pin "2") (pinfunction "2_2") (pintype "passive"))
      (node (ref "S225") (pin "2") (pinfunction "2_2") (pintype "passive"))
      (node (ref "S242") (pin "2") (pinfunction "2_2") (pintype "passive"))
      (node (ref "S259") (pin "2") (pinfunction "2_2") (pintype "passive"))
      (node (ref "S273") (pin "2") (pinfunction "2_2") (pintype "passive"))
    )
    (net (code "10") (name "/col10") (class "Default")
      (node (ref "S209") (pin "2") (pinfunction "2_2") (pintype "passive"))
      (node (ref "S226") (pin "2") (pinfunction "2_2") (pintype "passive"))
      (node (ref "S243") (pin "2") (pinfunction "2_2") (pintype "passive"))
      (node (ref "S260") (pin "2") (pinfunction "2_2") (pintype "passive"))
      (node (ref "S274") (pin "2") (pinfunction "2_2") (pintype "passive"))
    )
    (net (code "11") (name "/col11") (class "Default")
      (node (ref "S210") (pin "2") (pinfunction "2_2") (pintype "passive"))
      (node (ref "S227") (pin "2") (pinfunction "2_2") (pintype "passive"))
      (node (ref "S244") (pin "2") (pinfunction "2_2") (pintype "passive"))
      (node (ref "S261") (pin "2") (pinfunction "2_2") (pintype "passive"))
      (node (ref "S275") (pin "2") (pinfunction "2_2") (pintype "passive"))
    )
    (net (code "12") (name "/col12") (class "Default")
      (node (ref "S211") (pin "2") (pinfunction "2_2") (pintype "passive"))
      (node (ref "S228") (pin "2") (pinfunction "2_2") (pintype "passive"))
      (node (ref "S245") (pin "2") (pinfunction "2_2") (pintype "passive"))
      (node (ref "S262") (pin "2") (pinfunction "2_2") (pintype "passive"))
      (node (ref "S276") (pin "2") (pinfunction "2_2") (pintype "passive"))
      (node (ref "S284") (pin "2") (pinfunction "2_2") (pintype "passive"))
    )
    (net (code "13") (name "/col13") (class "Default")
      (node (ref "S212") (pin "2") (pinfunction "2_2") (pintype "passive"))
      (node (ref "S229") (pin "2") (pinfunction "2_2") (pintype "passive"))
      (node (ref "S246") (pin "2") (pinfunction "2_2") (pintype "passive"))
      (node (ref "S263") (pin "2") (pinfunction "2_2") (pintype "passive"))
      (node (ref "S277") (pin "2") (pinfunction "2_2") (pintype "passive"))
      (node (ref "S285") (pin "2") (pinfunction "2_2") (pintype "passive"))
    )
    (net (code "14") (name "/col14") (class "Default")
      (node (ref "S213") (pin "2") (pinfunction "2_2") (pintype "passive"))
      (node (ref "S230") (pin "2") (pinfunction "2_2") (pintype "passive"))
      (node (ref "S247") (pin "2") (pinfunction "2_2") (pintype "passive"))
      (node (ref "S264") (pin "2") (pinfunction "2_2") (pintype "passive"))
      (node (ref "S278") (pin "2") (pinfunction "2_2") (pintype "passive"))
      (node (ref "S286") (pin "2") (pinfunction "2_2") (pintype "passive"))
    )
    (net (code "15") (name "/col15") (class "Default")
      (node (ref "S214") (pin "2") (pinfunction "2_2") (pintype "passive"))
      (node (ref "S231") (pin "2") (pinfunction "2_2") (pintype "passive"))
      (node (ref "S248") (pin "2") (pinfunction "2_2") (pintype "passive"))
      (node (ref "S287") (pin "2") (pinfunction "2_2") (pintype "passive"))
    )
    (net (code "16") (name "/col16") (class "Default")
      (node (ref "S215") (pin "2") (pinfunction "2_2") (pintype "passive"))
      (node (ref "S232") (pin "2") (pinfunction "2_2") (pintype "passive"))
      (node (ref "S249") (pin "2") (pinfunction "2_2") (pintype "passive"))
      (node (ref "S279") (pin "2") (pinfunction "2_2") (pintype "passive"))
      (node (ref "S288") (pin "2") (pinfunction "2_2") (pintype "passive"))
    )
    (net (code "17") (name "/col17") (class "Default")
      (node (ref "S216") (pin "2") (pinfunction "2_2") (pintype "passive"))
      (node (ref "S233") (pin "2") (pinfunction "2_2") (pintype "passive"))
      (node (ref "S250") (pin "2") (pinfunction "2_2") (pintype "passive"))
      (node (ref "S289") (pin "2") (pinfunction "2_2") (pintype "passive"))
    )
    (net (code "18") (name "/row1") (class "Default")
      (node (ref "D201") (pin "2") (pinfunction "K_2") (pintype "passive"))
      (node (ref "D202") (pin "2") (pinfunction "K_2") (pintype "passive"))
      (node (ref "D203") (pin "2") (pinfunction "K_2") (pintype "passive"))
      (node (ref "D204") (pin "2") (pinfunction "K_2") (pintype "passive"))
      (node (ref "D205") (pin "2") (pinfunction "K_2") (pintype "passive"))
      (node (ref "D206") (pin "2") (pinfunction "K_2") (pintype "passive"))
      (node (ref "D207") (pin "2") (pinfunction "K_2") (pintype "passive"))
      (node (ref "D208") (pin "2") (pinfunction "K_2") (pintype "passive"))
      (node (ref "D209") (pin "2") (pinfunction "K_2") (pintype "passive"))
      (node (ref "D210") (pin "2") (pinfunction "K_2") (pintype "passive"))
      (node (ref "D211") (pin "2") (pinfunction "K_2") (pintype "passive"))
      (node (ref "D212") (pin "2") (pinfunction "K_2") (pintype "passive"))
      (node (ref "D213") (pin "2") (pinfunction "K_2") (pintype "passive"))
      (node (ref "D214") (pin "2") (pinfunction "K_2") (pintype "passive"))
      (node (ref "D215") (pin "2") (pinfunction "K_2") (pintype "passive"))
      (node (ref "D216") (pin "2") (pinfunction "K_2") (pintype "passive"))
    )
    (net (code "19") (name "/row2") (class "Default")
      (node (ref "D217") (pin "2") (pinfunction "K_2") (pintype "passive"))
      (node (ref "D218") (pin "2") (pinfunction "K_2") (pintype "passive"))
      (node (ref "D219") (pin "2") (pinfunction "K_2") (pintype "passive"))
      (node (ref "D220") (pin "2") (pinfunction "K_2") (pintype "passive"))
      (node (ref "D221") (pin "2") (pinfunction "K_2") (pintype "passive"))
      (node (ref "D222") (pin "2") (pinfunction "K_2") (pintype "passive"))
      (node (ref "D223") (pin "2") (pinfunction "K_2") (pintype "passive"))
      (node (ref "D224") (pin "2") (pinfunction "K_2") (pintype "passive"))
      (node (ref "D225") (pin "2") (pinfunction "K_2") (pintype "passive"))
      (node (ref "D226") (pin "2") (pinfunction "K_2") (pintype "passive"))
      (node (ref "D227") (pin "2") (pinfunction "K_2") (pintype "passive"))
      (node (ref "D228") (pin "2") (pinfunction "K_2") (pintype "passive"))
      (node (ref "D229") (pin "2") (pinfunction "K_2") (pintype "passive"))
      (node (ref "D230") (pin "2") (pinfunction "K_2") (pintype "passive"))
      (node (ref "D231") (pin "2") (pinfunction "K_2") (pintype "passive"))
      (node (ref "D232") (pin "2") (pinfunction "K_2") (pintype "passive"))
      (node (ref "D233") (pin "2") (pinfunction "K_2") (pintype "passive"))
    )
    (net (code "20") (name "/row3") (class "Default")
      (node (ref "D234") (pin "2") (pinfunction "K_2") (pintype "passive"))
      (node (ref "D235") (pin "2") (pinfunction "K_2") (pintype "passive"))
      (node (ref "D236") (pin "2") (pinfunction "K_2") (pintype "passive"))
      (node (ref "D237") (pin "2") (pinfunction "K_2") (pintype "passive"))
      (node (ref "D238") (pin "2") (pinfunction "K_2") (pintype "passive"))
      (node (ref "D239") (pin "2") (pinfunction "K_2") (pintype "passive"))
      (node (ref "D240") (pin "2") (pinfunction "K_2") (pintype "passive"))
      (node (ref "D241") (pin "2") (pinfunction "K_2") (pintype "passive"))
      (node (ref "D242") (pin "2") (pinfunction "K_2") (pintype "passive"))
      (node (ref "D243") (pin "2") (pinfunction "K_2") (pintype "passive"))
      (node (ref "D244") (pin "2") (pinfunction "K_2") (pintype "passive"))
      (node (ref "D245") (pin "2") (pinfunction "K_2") (pintype "passive"))
      (node (ref "D246") (pin "2") (pinfunction "K_2") (pintype "passive"))
      (node (ref "D247") (pin "2") (pinfunction "K_2") (pintype "passive"))
      (node (ref "D248") (pin "2") (pinfunction "K_2") (pintype "passive"))
      (node (ref "D249") (pin "2") (pinfunction "K_2") (pintype "passive"))
      (node (ref "D250") (pin "2") (pinfunction "K_2") (pintype "passive"))
    )
    (net (code "21") (name "/row4") (class "Default")
      (node (ref "D251") (pin "2") (pinfunction "K_2") (pintype "passive"))
      (node (ref "D252") (pin "2") (pinfunction "K_2") (pintype "passive"))
      (node (ref "D253") (pin "2") (pinfunction "K_2") (pintype "passive"))
      (node (ref "D254") (pin "2") (pinfunction "K_2") (pintype "passive"))
      (node (ref "D255") (pin "2") (pinfunction "K_2") (pintype "passive"))
      (node (ref "D256") (pin "2") (pinfunction "K_2") (pintype "passive"))
      (node (ref "D257") (pin "2") (pinfunction "K_2") (pintype "passive"))
      (node (ref "D258") (pin "2") (pinfunction "K_2") (pintype "passive"))
      (node (ref "D259") (pin "2") (pinfunction "K_2") (pintype "passive"))
      (node (ref "D260") (pin "2") (pinfunction "K_2") (pintype "passive"))
      (node (ref "D261") (pin "2") (pinfunction "K_2") (pintype "passive"))
      (node (ref "D262") (pin "2") (pinfunction "K_2") (pintype "passive"))
      (node (ref "D263") (pin "2") (pinfunction "K_2") (pintype "passive"))
      (node (ref "D264") (pin "2") (pinfunction "K_2") (pintype "passive"))
    )
    (net (code "22") (name "/row5") (class "Default")
      (node (ref "D265") (pin "2") (pinfunction "K_2") (pintype "passive"))
      (node (ref "D266") (pin "2") (pinfunction "K_2") (pintype "passive"))
      (node (ref "D267") (pin "2") (pinfunction "K_2") (pintype "passive"))
      (node (ref "D268") (pin "2") (pinfunction "K_2") (pintype "passive"))
      (node (ref "D269") (pin "2") (pinfunction "K_2") (pintype "passive"))
      (node (ref "D270") (pin "2") (pinfunction "K_2") (pintype "passive"))
      (node (ref "D271") (pin "2") (pinfunction "K_2") (pintype "passive"))
      (node (ref "D272") (pin "2") (pinfunction "K_2") (pintype "passive"))
      (node (ref "D273") (pin "2") (pinfunction "K_2") (pintype "passive"))
      (node (ref "D274") (pin "2") (pinfunction "K_2") (pintype "passive"))
      (node (ref "D275") (pin "2") (pinfunction "K_2") (pintype "passive"))
      (node (ref "D276") (pin "2") (pinfunction "K_2") (pintype "passive"))
      (node (ref "D277") (pin "2") (pinfunction "K_2") (pintype "passive"))
      (node (ref "D278") (pin "2") (pinfunction "K_2") (pintype "passive"))
      (node (ref "D279") (pin "2") (pinfunction "K_2") (pintype "passive"))
    )
    (net (code "23") (name "/row6") (class "Default")
      (node (ref "D280") (pin "2") (pinfunction "K_2") (pintype "passive"))
      (node (ref "D281") (pin "2") (pinfunction "K_2") (pintype "passive"))
      (node (ref "D282") (pin "2") (pinfunction "K_2") (pintype "passive"))
      (node (ref "D283") (pin "2") (pinfunction "K_2") (pintype "passive"))
      (node (ref "D284") (pin "2") (pinfunction "K_2") (pintype "passive"))
      (node (ref "D285") (pin "2") (pinfunction "K_2") (pintype "passive"))
      (node (ref "D286") (pin "2") (pinfunction "K_2") (pintype "passive"))
      (node (ref "D287") (pin "2") (pinfunction "K_2") (pintype "passive"))
      (node (ref "D288") (pin "2") (pinfunction "K_2") (pintype "passive"))
      (node (ref "D289") (pin "2") (pinfunction "K_2") (pintype "passive"))
    )
    (net (code "24") (name "Net-(D201-A)") (class "Default")
      (node (ref "D201") (pin "1") (pinfunction "A_1") (pintype "passive"))
      (node (ref "S201") (pin "1") (pinfunction "1_1") (pintype "passive"))
    )
    (net (code "25") (name "Net-(D202-A)") (class "Default")
      (node (ref "D202") (pin "1") (pinfunction "A_1") (pintype "passive"))
      (node (ref "S202") (pin "1") (pinfunction "1_1") (pintype "passive"))
    )
    (net (code "26") (name "Net-(D203-A)") (class "Default")
      (node (ref "D203") (pin "1") (pinfunction "A_1") (pintype "passive"))
      (node (ref "S203") (pin "1") (pinfunction "1_1") (pintype "passive"))
    )
    (net (code "27") (name "Net-(D204-A)") (class "Default")
      (node (ref "D204") (pin "1") (pinfunction "A_1") (pintype "passive"))
      (node (ref "S204") (pin "1") (pinfunction "1_1") (pintype "passive"))
    )
    (net (code "28") (name "Net-(D205-A)") (class "Default")
      (node (ref "D205") (pin "1") (pinfunction "A_1") (pintype "passive"))
      (node (ref "S205") (pin "1") (pinfunction "1_1") (pintype "passive"))
    )
    (net (code "29") (name "Net-(D206-A)") (class "Default")
      (node (ref "D206") (pin "1") (pinfunction "A_1") (pintype "passive"))
      (node (ref "S206") (pin "1") (pinfunction "1_1") (pintype "passive"))
    )
    (net (code "30") (name "Net-(D207-A)") (class "Default")
      (node (ref "D207") (pin "1") (pinfunction "A_1") (pintype "passive"))
      (node (ref "S207") (pin "1") (pinfunction "1_1") (pintype "passive"))
    )
    (net (code "31") (name "Net-(D208-A)") (class "Default")
      (node (ref "D208") (pin "1") (pinfunction "A_1") (pintype "passive"))
      (node (ref "S208") (pin "1") (pinfunction "1_1") (pintype "passive"))
    )
    (net (code "32") (name "Net-(D209-A)") (class "Default")
      (node (ref "D209") (pin "1") (pinfunction "A_1") (pintype "passive"))
      (node (ref "S209") (pin "1") (pinfunction "1_1") (pintype "passive"))
    )
    (net (code "33") (name "Net-(D210-A)") (class "Default")
      (node (ref "D210") (pin "1") (pinfunction "A_1") (pintype "passive"))
      (node (ref "S210") (pin "1") (pinfunction "1_1") (pintype "passive"))
    )
    (net (code "34") (name "Net-(D211-A)") (class "Default")
      (node (ref "D211") (pin "1") (pinfunction "A_1") (pintype "passive"))
      (node (ref "S211") (pin "1") (pinfunction "1_1") (pintype "passive"))
    )
    (net (code "35") (name "Net-(D212-A)") (class "Default")
      (node (ref "D212") (pin "1") (pinfunction "A_1") (pintype "passive"))
      (node (ref "S212") (pin "1") (pinfunction "1_1") (pintype "passive"))
    )
    (net (code "36") (name "Net-(D213-A)") (class "Default")
      (node (ref "D213") (pin "1") (pinfunction "A_1") (pintype "passive"))
      (node (ref "S213") (pin "1") (pinfunction "1_1") (pintype "passive"))
    )
    (net (code "37") (name "Net-(D214-A)") (class "Default")
      (node (ref "D214") (pin "1") (pinfunction "A_1") (pintype "passive"))
      (node (ref "S214") (pin "1") (pinfunction "1_1") (pintype "passive"))
    )
    (net (code "38") (name "Net-(D215-A)") (class "Default")
      (node (ref "D215") (pin "1") (pinfunction "A_1") (pintype "passive"))
      (node (ref "S215") (pin "1") (pinfunction "1_1") (pintype "passive"))
    )
    (net (code "39") (name "Net-(D216-A)") (class "Default")
      (node (ref "D216") (pin "1") (pinfunction "A_1") (pintype "passive"))
      (node (ref "S216") (pin "1") (pinfunction "1_1") (pintype "passive"))
    )
    (net (code "40") (name "Net-(D217-A)") (class "Default")
      (node (ref "D217") (pin "1") (pinfunction "A_1") (pintype "passive"))
      (node (ref "S217") (pin "1") (pinfunction "1_1") (pintype "passive"))
    )
    (net (code "41") (name "Net-(D218-A)") (class "Default")
      (node (ref "D218") (pin "1") (pinfunction "A_1") (pintype "passive"))
      (node (ref "S218") (pin "1") (pinfunction "1_1") (pintype "passive"))
    )
    (net (code "42") (name "Net-(D219-A)") (class "Default")
      (node (ref "D219") (pin "1") (pinfunction "A_1") (pintype "passive"))
      (node (ref "S219") (pin "1") (pinfunction "1_1") (pintype "passive"))
    )
    (net (code "43") (name "Net-(D220-A)") (class "Default")
      (node (ref "D220") (pin "1") (pinfunction "A_1") (pintype "passive"))
      (node (ref "S220") (pin "1") (pinfunction "1_1") (pintype "passive"))
    )
    (net (code "44") (name "Net-(D221-A)") (class "Default")
      (node (ref "D221") (pin "1") (pinfunction "A_1") (pintype "passive"))
      (node (ref "S221") (pin "1") (pinfunction "1_1") (pintype "passive"))
    )
    (net (code "45") (name "Net-(D222-A)") (class "Default")
      (node (ref "D222") (pin "1") (pinfunction "A_1") (pintype "passive"))
      (node (ref "S222") (pin "1") (pinfunction "1_1") (pintype "passive"))
    )
    (net (code "46") (name "Net-(D223-A)") (class "Default")
      (node (ref "D223") (pin "1") (pinfunction "A_1") (pintype "passive"))
      (node (ref "S223") (pin "1") (pinfunction "1_1") (pintype "passive"))
    )
    (net (code "47") (name "Net-(D224-A)") (class "Default")
      (node (ref "D224") (pin "1") (pinfunction "A_1") (pintype "passive"))
      (node (ref "S224") (pin "1") (pinfunction "1_1") (pintype "passive"))
    )
    (net (code "48") (name "Net-(D225-A)") (class "Default")
      (node (ref "D225") (pin "1") (pinfunction "A_1") (pintype "passive"))
      (node (ref "S225") (pin "1") (pinfunction "1_1") (pintype "passive"))
    )
    (net (code "49") (name "Net-(D226-A)") (class "Default")
      (node (ref "D226") (pin "1") (pinfunction "A_1") (pintype "passive"))
      (node (ref "S226") (pin "1") (pinfunction "1_1") (pintype "passive"))
    )
    (net (code "50") (name "Net-(D227-A)") (class "Default")
      (node (ref "D227") (pin "1") (pinfunction "A_1") (pintype "passive"))
      (node (ref "S227") (pin "1") (pinfunction "1_1") (pintype "passive"))
    )
    (net (code "51") (name "Net-(D228-A)") (class "Default")
      (node (ref "D228") (pin "1") (pinfunction "A_1") (pintype "passive"))
      (node (ref "S228") (pin "1") (pinfunction "1_1") (pintype "passive"))
    )
    (net (code "52") (name "Net-(D229-A)") (class "Default")
      (node (ref "D229") (pin "1") (pinfunction "A_1") (pintype "passive"))
      (node (ref "S229") (pin "1") (pinfunction "1_1") (pintype "passive"))
    )
    (net (code "53") (name "Net-(D230-A)") (class "Default")
      (node (ref "D230") (pin "1") (pinfunction "A_1") (pintype "passive"))
      (node (ref "S230") (pin "1") (pinfunction "1_1") (pintype "passive"))
    )
    (net (code "54") (name "Net-(D231-A)") (class "Default")
      (node (ref "D231") (pin "1") (pinfunction "A_1") (pintype "passive"))
      (node (ref "S231") (pin "1") (pinfunction "1_1") (pintype "passive"))
    )
    (net (code "55") (name "Net-(D232-A)") (class "Default")
      (node (ref "D232") (pin "1") (pinfunction "A_1") (pintype "passive"))
      (node (ref "S232") (pin "1") (pinfunction "1_1") (pintype "passive"))
    )
    (net (code "56") (name "Net-(D233-A)") (class "Default")
      (node (ref "D233") (pin "1") (pinfunction "A_1") (pintype "passive"))
      (node (ref "S233") (pin "1") (pinfunction "1_1") (pintype "passive"))
    )
    (net (code "57") (name "Net-(D234-A)") (class "Default")
      (node (ref "D234") (pin "1") (pinfunction "A_1") (pintype "passive"))
      (node (ref "S234") (pin "1") (pinfunction "1_1") (pintype "passive"))
    )
    (net (code "58") (name "Net-(D235-A)") (class "Default")
      (node (ref "D235") (pin "1") (pinfunction "A_1") (pintype "passive"))
      (node (ref "S235") (pin "1") (pinfunction "1_1") (pintype "passive"))
    )
    (net (code "59") (name "Net-(D236-A)") (class "Default")
      (node (ref "D236") (pin "1") (pinfunction "A_1") (pintype "passive"))
      (node (ref "S236") (pin "1") (pinfunction "1_1") (pintype "passive"))
    )
    (net (code "60") (name "Net-(D237-A)") (class "Default")
      (node (ref "D237") (pin "1") (pinfunction "A_1") (pintype "passive"))
      (node (ref "S237") (pin "1") (pinfunction "1_1") (pintype "passive"))
    )
    (net (code "61") (name "Net-(D238-A)") (class "Default")
      (node (ref "D238") (pin "1") (pinfunction "A_1") (pintype "passive"))
      (node (ref "S238") (pin "1") (pinfunction "1_1") (pintype "passive"))
    )
    (net (code "62") (name "Net-(D239-A)") (class "Default")
      (node (ref "D239") (pin "1") (pinfunction "A_1") (pintype "passive"))
      (node (ref "S239") (pin "1") (pinfunction "1_1") (pintype "passive"))
    )
    (net (code "63") (name "Net-(D240-A)") (class "Default")
      (node (ref "D240") (pin "1") (pinfunction "A_1") (pintype "passive"))
      (node (ref "S240") (pin "1") (pinfunction "1_1") (pintype "passive"))
    )
    (net (code "64") (name "Net-(D241-A)") (class "Default")
      (node (ref "D241") (pin "1") (pinfunction "A_1") (pintype "passive"))
      (node (ref "S241") (pin "1") (pinfunction "1_1") (pintype "passive"))
    )
    (net (code "65") (name "Net-(D242-A)") (class "Default")
      (node (ref "D242") (pin "1") (pinfunction "A_1") (pintype "passive"))
      (node (ref "S242") (pin "1") (pinfunction "1_1") (pintype "passive"))
    )
    (net (code "66") (name "Net-(D243-A)") (class "Default")
      (node (ref "D243") (pin "1") (pinfunction "A_1") (pintype "passive"))
      (node (ref "S243") (pin "1") (pinfunction "1_1") (pintype "passive"))
    )
    (net (code "67") (name "Net-(D244-A)") (class "Default")
      (node (ref "D244") (pin "1") (pinfunction "A_1") (pintype "passive"))
      (node (ref "S244") (pin "1") (pinfunction "1_1") (pintype "passive"))
    )
    (net (code "68") (name "Net-(D245-A)") (class "Default")
      (node (ref "D245") (pin "1") (pinfunction "A_1") (pintype "passive"))
      (node (ref "S245") (pin "1") (pinfunction "1_1") (pintype "passive"))
    )
    (net (code "69") (name "Net-(D246-A)") (class "Default")
      (node (ref "D246") (pin "1") (pinfunction "A_1") (pintype "passive"))
      (node (ref "S246") (pin "1") (pinfunction "1_1") (pintype "passive"))
    )
    (net (code "70") (name "Net-(D247-A)") (class "Default")
      (node (ref "D247") (pin "1") (pinfunction "A_1") (pintype "passive"))
      (node (ref "S247") (pin "1") (pinfunction "1_1") (pintype "passive"))
    )
    (net (code "71") (name "Net-(D248-A)") (class "Default")
      (node (ref "D248") (pin "1") (pinfunction "A_1") (pintype "passive"))
      (node (ref "S248") (pin "1") (pinfunction "1_1") (pintype "passive"))
    )
    (net (code "72") (name "Net-(D249-A)") (class "Default")
      (node (ref "D249") (pin "1") (pinfunction "A_1") (pintype "passive"))
      (node (ref "S249") (pin "1") (pinfunction "1_1") (pintype "passive"))
    )
    (net (code "73") (name "Net-(D250-A)") (class "Default")
      (node (ref "D250") (pin "1") (pinfunction "A_1") (pintype "passive"))
      (node (ref "S250") (pin "1") (pinfunction "1_1") (pintype "passive"))
    )
    (net (code "74") (name "Net-(D251-A)") (class "Default")
      (node (ref "D251") (pin "1") (pinfunction "A_1") (pintype "passive"))
      (node (ref "S251") (pin "1") (pinfunction "1_1") (pintype "passive"))
    )
    (net (code "75") (name "Net-(D252-A)") (class "Default")
      (node (ref "D252") (pin "1") (pinfunction "A_1") (pintype "passive"))
      (node (ref "S252") (pin "1") (pinfunction "1_1") (pintype "passive"))
    )
    (net (code "76") (name "Net-(D253-A)") (class "Default")
      (node (ref "D253") (pin "1") (pinfunction "A_1") (pintype "passive"))
      (node (ref "S253") (pin "1") (pinfunction "1_1") (pintype "passive"))
    )
    (net (code "77") (name "Net-(D254-A)") (class "Default")
      (node (ref "D254") (pin "1") (pinfunction "A_1") (pintype "passive"))
      (node (ref "S254") (pin "1") (pinfunction "1_1") (pintype "passive"))
    )
    (net (code "78") (name "Net-(D255-A)") (class "Default")
      (node (ref "D255") (pin "1") (pinfunction "A_1") (pintype "passive"))
      (node (ref "S255") (pin "1") (pinfunction "1_1") (pintype "passive"))
    )
    (net (code "79") (name "Net-(D256-A)") (class "Default")
      (node (ref "D256") (pin "1") (pinfunction "A_1") (pintype "passive"))
      (node (ref "S256") (pin "1") (pinfunction "1_1") (pintype "passive"))
    )
    (net (code "80") (name "Net-(D257-A)") (class "Default")
      (node (ref "D257") (pin "1") (pinfunction "A_1") (pintype "passive"))
      (node (ref "S257") (pin "1") (pinfunction "1_1") (pintype "passive"))
    )
    (net (code "81") (name "Net-(D258-A)") (class "Default")
      (node (ref "D258") (pin "1") (pinfunction "A_1") (pintype "passive"))
      (node (ref "S258") (pin "1") (pinfunction "1_1") (pintype "passive"))
    )
    (net (code "82") (name "Net-(D259-A)") (class "Default")
      (node (ref "D259") (pin "1") (pinfunction "A_1") (pintype "passive"))
      (node (ref "S259") (pin "1") (pinfunction "1_1") (pintype "passive"))
    )
    (net (code "83") (name "Net-(D260-A)") (class "Default")
      (node (ref "D260") (pin "1") (pinfunction "A_1") (pintype "passive"))
      (node (ref "S260") (pin "1") (pinfunction "1_1") (pintype "passive"))
    )
    (net (code "84") (name "Net-(D261-A)") (class "Default")
      (node (ref "D261") (pin "1") (pinfunction "A_1") (pintype "passive"))
      (node (ref "S261") (pin "1") (pinfunction "1_1") (pintype "passive"))
    )
    (net (code "85") (name "Net-(D262-A)") (class "Default")
      (node (ref "D262") (pin "1") (pinfunction "A_1") (pintype "passive"))
      (node (ref "S262") (pin "1") (pinfunction "1_1") (pintype "passive"))
    )
    (net (code "86") (name "Net-(D263-A)") (class "Default")
      (node (ref "D263") (pin "1") (pinfunction "A_1") (pintype "passive"))
      (node (ref "S263") (pin "1") (pinfunction "1_1") (pintype "passive"))
    )
    (net (code "87") (name "Net-(D264-A)") (class "Default")
      (node (ref "D264") (pin "1") (pinfunction "A_1") (pintype "passive"))
      (node (ref "S264") (pin "1") (pinfunction "1_1") (pintype "passive"))
    )
    (net (code "88") (name "Net-(D265-A)") (class "Default")
      (node (ref "D265") (pin "1") (pinfunction "A_1") (pintype "passive"))
      (node (ref "S265") (pin "1") (pinfunction "1_1") (pintype "passive"))
    )
    (net (code "89") (name "Net-(D266-A)") (class "Default")
      (node (ref "D266") (pin "1") (pinfunction "A_1") (pintype "passive"))
      (node (ref "S266") (pin "1") (pinfunction "1_1") (pintype "passive"))
    )
    (net (code "90") (name "Net-(D267-A)") (class "Default")
      (node (ref "D267") (pin "1") (pinfunction "A_1") (pintype "passive"))
      (node (ref "S267") (pin "1") (pinfunction "1_1") (pintype "passive"))
    )
    (net (code "91") (name "Net-(D268-A)") (class "Default")
      (node (ref "D268") (pin "1") (pinfunction "A_1") (pintype "passive"))
      (node (ref "S268") (pin "1") (pinfunction "1_1") (pintype "passive"))
    )
    (net (code "92") (name "Net-(D269-A)") (class "Default")
      (node (ref "D269") (pin "1") (pinfunction "A_1") (pintype "passive"))
      (node (ref "S269") (pin "1") (pinfunction "1_1") (pintype "passive"))
    )
    (net (code "93") (name "Net-(D270-A)") (class "Default")
      (node (ref "D270") (pin "1") (pinfunction "A_1") (pintype "passive"))
      (node (ref "S270") (pin "1") (pinfunction "1_1") (pintype "passive"))
    )
    (net (code "94") (name "Net-(D271-A)") (class "Default")
      (node (ref "D271") (pin "1") (pinfunction "A_1") (pintype "passive"))
      (node (ref "S271") (pin "1") (pinfunction "1_1") (pintype "passive"))
    )
    (net (code "95") (name "Net-(D272-A)") (class "Default")
      (node (ref "D272") (pin "1") (pinfunction "A_1") (pintype "passive"))
      (node (ref "S272") (pin "1") (pinfunction "1_1") (pintype "passive"))
    )
    (net (code "96") (name "Net-(D273-A)") (class "Default")
      (node (ref "D273") (pin "1") (pinfunction "A_1") (pintype "passive"))
      (node (ref "S273") (pin "1") (pinfunction "1_1") (pintype "passive"))
    )
    (net (code "97") (name "Net-(D274-A)") (class "Default")
      (node (ref "D274") (pin "1") (pinfunction "A_1") (pintype "passive"))
      (node (ref "S274") (pin "1") (pinfunction "1_1") (pintype "passive"))
    )
    (net (code "98") (name "Net-(D275-A)") (class "Default")
      (node (ref "D275") (pin "1") (pinfunction "A_1") (pintype "passive"))
      (node (ref "S275") (pin "1") (pinfunction "1_1") (pintype "passive"))
    )
    (net (code "99") (name "Net-(D276-A)") (class "Default")
      (node (ref "D276") (pin "1") (pinfunction "A_1") (pintype "passive"))
      (node (ref "S276") (pin "1") (pinfunction "1_1") (pintype "passive"))
    )
    (net (code "100") (name "Net-(D277-A)") (class "Default")
      (node (ref "D277") (pin "1") (pinfunction "A_1") (pintype "passive"))
      (node (ref "S277") (pin "1") (pinfunction "1_1") (pintype "passive"))
    )
    (net (code "101") (name "Net-(D278-A)") (class "Default")
      (node (ref "D278") (pin "1") (pinfunction "A_1") (pintype "passive"))
      (node (ref "S278") (pin "1") (pinfunction "1_1") (pintype "passive"))
    )
    (net (code "102") (name "Net-(D279-A)") (class "Default")
      (node (ref "D279") (pin "1") (pinfunction "A_1") (pintype "passive"))
      (node (ref "S279") (pin "1") (pinfunction "1_1") (pintype "passive"))
    )
    (net (code "103") (name "Net-(D280-A)") (class "Default")
      (node (ref "D280") (pin "1") (pinfunction "A_1") (pintype "passive"))
      (node (ref "S280") (pin "1") (pinfunction "1_1") (pintype "passive"))
    )
    (net (code "104") (name "Net-(D281-A)") (class "Default")
      (node (ref "D281") (pin "1") (pinfunction "A_1") (pintype "passive"))
      (node (ref "S281") (pin "1") (pinfunction "1_1") (pintype "passive"))
    )
    (net (code "105") (name "Net-(D282-A)") (class "Default")
      (node (ref "D282") (pin "1") (pinfunction "A_1") (pintype "passive"))
      (node (ref "S282") (pin "1") (pinfunction "1_1") (pintype "passive"))
    )
    (net (code "106") (name "Net-(D283-A)") (class "Default")
      (node (ref "D283") (pin "1") (pinfunction "A_1") (pintype "passive"))
      (node (ref "S283") (pin "1") (pinfunction "1_1") (pintype "passive"))
    )
    (net (code "107") (name "Net-(D284-A)") (class "Default")
      (node (ref "D284") (pin "1") (pinfunction "A_1") (pintype "passive"))
      (node (ref "S284") (pin "1") (pinfunction "1_1") (pintype "passive"))
    )
    (net (code "108") (name "Net-(D285-A)") (class "Default")
      (node (ref "D285") (pin "1") (pinfunction "A_1") (pintype "passive"))
      (node (ref "S285") (pin "1") (pinfunction "1_1") (pintype "passive"))
    )
    (net (code "109") (name "Net-(D286-A)") (class "Default")
      (node (ref "D286") (pin "1") (pinfunction "A_1") (pintype "passive"))
      (node (ref "S286") (pin "1") (pinfunction "1_1") (pintype "passive"))
    )
    (net (code "110") (name "Net-(D287-A)") (class "Default")
      (node (ref "D287") (pin "1") (pinfunction "A_1") (pintype "passive"))
      (node (ref "S287") (pin "1") (pinfunction "1_1") (pintype "passive"))
    )
    (net (code "111") (name "Net-(D288-A)") (class "Default")
      (node (ref "D288") (pin "1") (pinfunction "A_1") (pintype "passive"))
      (node (ref "S288") (pin "1") (pinfunction "1_1") (pintype "passive"))
    )
    (net (code "112") (name "Net-(D289-A)") (class "Default")
      (node (ref "D289") (pin "1") (pinfunction "A_1") (pintype "passive"))
      (node (ref "S289") (pin "1") (pinfunction "1_1") (pintype "passive"))
    )
  )
)
